# 06_-_INPUT.net
KiCad netlist of a schematic drawn in Altium Designer
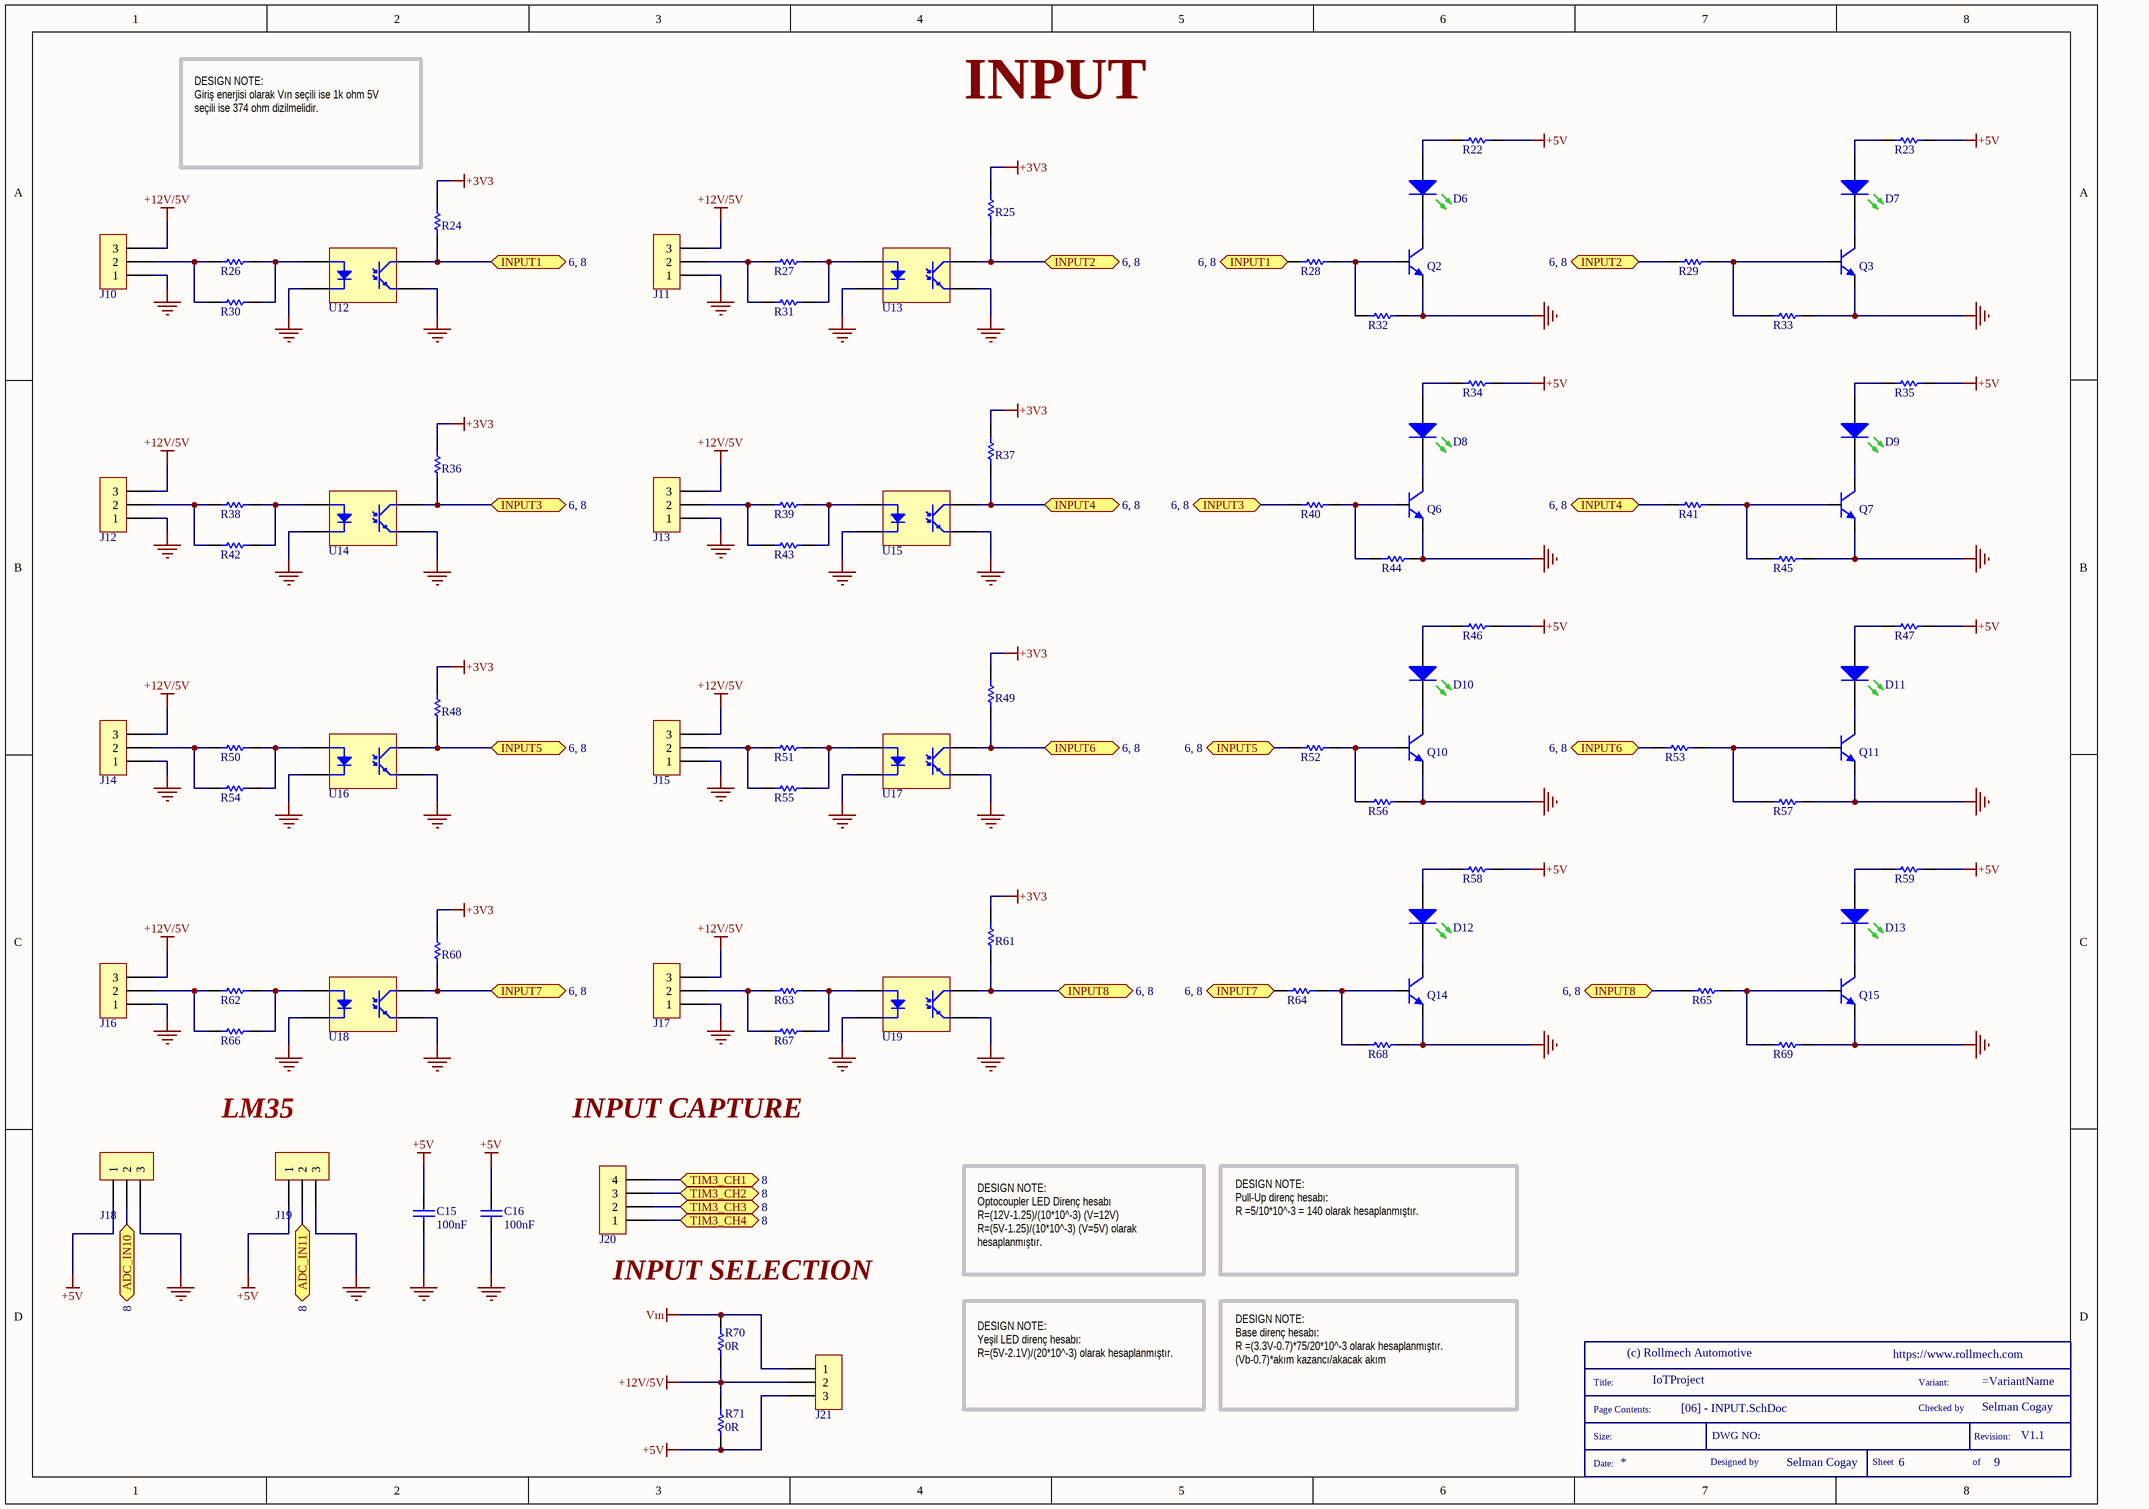
[diagram p0: [06] - INPUT.SchDoc]

(export (version "E")
  (design (tool "Eeschema 10.0.6"))
  (components
    (comp (ref "C15")
      (value "100nF")
      (footprint "C0603")
      (description "CAP CER 0.1UF 25V X7R 0603")
      (libsource (lib "SN65HVD2xx-CAN-Module-V1I1") (part "CGA3E2X7R1E104K080AA"))
    )
    (comp (ref "C16")
      (value "100nF")
      (footprint "C0603")
      (description "CAP CER 0.1UF 25V X7R 0603")
      (libsource (lib "SN65HVD2xx-CAN-Module-V1I1") (part "CGA3E2X7R1E104K080AA"))
    )
    (comp (ref "D6")
      (value "LED GREEN")
      (footprint "PLCC2")
      (description "LED TOPLED GREEN 562NM 2PLCC")
      (libsource (lib "Rollmech_Altium") (part "LP T67F-P1R2-35-1-20-R18-Z"))
    )
    (comp (ref "D7")
      (value "LED GREEN")
      (footprint "PLCC2")
      (description "LED TOPLED GREEN 562NM 2PLCC")
      (libsource (lib "Rollmech_Altium") (part "LP T67F-P1R2-35-1-20-R18-Z"))
    )
    (comp (ref "D8")
      (value "LED GREEN")
      (footprint "PLCC2")
      (description "LED TOPLED GREEN 562NM 2PLCC")
      (libsource (lib "Rollmech_Altium") (part "LP T67F-P1R2-35-1-20-R18-Z"))
    )
    (comp (ref "D9")
      (value "LED GREEN")
      (footprint "PLCC2")
      (description "LED TOPLED GREEN 562NM 2PLCC")
      (libsource (lib "Rollmech_Altium") (part "LP T67F-P1R2-35-1-20-R18-Z"))
    )
    (comp (ref "D10")
      (value "LED GREEN")
      (footprint "PLCC2")
      (description "LED TOPLED GREEN 562NM 2PLCC")
      (libsource (lib "Rollmech_Altium") (part "LP T67F-P1R2-35-1-20-R18-Z"))
    )
    (comp (ref "D11")
      (value "LED GREEN")
      (footprint "PLCC2")
      (description "LED TOPLED GREEN 562NM 2PLCC")
      (libsource (lib "Rollmech_Altium") (part "LP T67F-P1R2-35-1-20-R18-Z"))
    )
    (comp (ref "D12")
      (value "LED GREEN")
      (footprint "PLCC2")
      (description "LED TOPLED GREEN 562NM 2PLCC")
      (libsource (lib "Rollmech_Altium") (part "LP T67F-P1R2-35-1-20-R18-Z"))
    )
    (comp (ref "D13")
      (value "LED GREEN")
      (footprint "PLCC2")
      (description "LED TOPLED GREEN 562NM 2PLCC")
      (libsource (lib "Rollmech_Altium") (part "LP T67F-P1R2-35-1-20-R18-Z"))
    )
    (comp (ref "J10")
      (value "CONN 1X3 3MM")
      (footprint "CONN_MALE_1X3_3MM")
      (description "CONN MALE 1X3 3MM")
      (libsource (lib "Rollmech_Altium") (part "66200311122"))
    )
    (comp (ref "J11")
      (value "CONN 1X3 3MM")
      (footprint "CONN_MALE_1X3_3MM")
      (description "CONN MALE 1X3 3MM")
      (libsource (lib "Rollmech_Altium") (part "66200311122"))
    )
    (comp (ref "J12")
      (value "CONN 1X3 3MM")
      (footprint "CONN_MALE_1X3_3MM")
      (description "CONN MALE 1X3 3MM")
      (libsource (lib "Rollmech_Altium") (part "66200311122"))
    )
    (comp (ref "J13")
      (value "CONN 1X3 3MM")
      (footprint "CONN_MALE_1X3_3MM")
      (description "CONN MALE 1X3 3MM")
      (libsource (lib "Rollmech_Altium") (part "66200311122"))
    )
    (comp (ref "J14")
      (value "CONN 1X3 3MM")
      (footprint "CONN_MALE_1X3_3MM")
      (description "CONN MALE 1X3 3MM")
      (libsource (lib "Rollmech_Altium") (part "66200311122"))
    )
    (comp (ref "J15")
      (value "CONN 1X3 3MM")
      (footprint "CONN_MALE_1X3_3MM")
      (description "CONN MALE 1X3 3MM")
      (libsource (lib "Rollmech_Altium") (part "66200311122"))
    )
    (comp (ref "J16")
      (value "CONN 1X3 3MM")
      (footprint "CONN_MALE_1X3_3MM")
      (description "CONN MALE 1X3 3MM")
      (libsource (lib "Rollmech_Altium") (part "66200311122"))
    )
    (comp (ref "J17")
      (value "CONN 1X3 3MM")
      (footprint "CONN_MALE_1X3_3MM")
      (description "CONN MALE 1X3 3MM")
      (libsource (lib "Rollmech_Altium") (part "66200311122"))
    )
    (comp (ref "J18")
      (value "HDR_1X3_2.54")
      (footprint "HDR_MALE_1X3_2.54MM")
      (description "HDR MALE 1X3 2.54MM")
      (libsource (lib "Rollmech_Altium") (part "61300311121"))
    )
    (comp (ref "J19")
      (value "HDR_1X3_2.54")
      (footprint "HDR_MALE_1X3_2.54MM")
      (description "HDR MALE 1X3 2.54MM")
      (libsource (lib "Rollmech_Altium") (part "61300311121"))
    )
    (comp (ref "J20")
      (value "HDR FEMALE 1X4 2.54MM")
      (footprint "HDR_FEMALE_1X4_2.54MM")
      (libsource (lib "Rollmech_Altium") (part "PPTC041LFBN-RC"))
    )
    (comp (ref "J21")
      (value "HDR_1X3_2.54")
      (footprint "HDR_MALE_1X3_2.54MM")
      (description "HDR MALE 1X3 2.54MM")
      (libsource (lib "") (part "61300311121_1"))
    )
    (comp (ref "Q2")
      (value "NPN 0.6A")
      (footprint "SOT-23 (TO-236)")
      (description "TRANS NPN 40V 0.6A SMD SOT23-3")
      (libsource (lib "Rollmech_Altium") (part "MMBT2222A-7-F"))
    )
    (comp (ref "Q3")
      (value "NPN 0.6A")
      (footprint "SOT-23 (TO-236)")
      (description "TRANS NPN 40V 0.6A SMD SOT23-3")
      (libsource (lib "Rollmech_Altium") (part "MMBT2222A-7-F"))
    )
    (comp (ref "Q6")
      (value "NPN 0.6A")
      (footprint "SOT-23 (TO-236)")
      (description "TRANS NPN 40V 0.6A SMD SOT23-3")
      (libsource (lib "Rollmech_Altium") (part "MMBT2222A-7-F"))
    )
    (comp (ref "Q7")
      (value "NPN 0.6A")
      (footprint "SOT-23 (TO-236)")
      (description "TRANS NPN 40V 0.6A SMD SOT23-3")
      (libsource (lib "Rollmech_Altium") (part "MMBT2222A-7-F"))
    )
    (comp (ref "Q10")
      (value "NPN 0.6A")
      (footprint "SOT-23 (TO-236)")
      (description "TRANS NPN 40V 0.6A SMD SOT23-3")
      (libsource (lib "Rollmech_Altium") (part "MMBT2222A-7-F"))
    )
    (comp (ref "Q11")
      (value "NPN 0.6A")
      (footprint "SOT-23 (TO-236)")
      (description "TRANS NPN 40V 0.6A SMD SOT23-3")
      (libsource (lib "Rollmech_Altium") (part "MMBT2222A-7-F"))
    )
    (comp (ref "Q14")
      (value "NPN 0.6A")
      (footprint "SOT-23 (TO-236)")
      (description "TRANS NPN 40V 0.6A SMD SOT23-3")
      (libsource (lib "Rollmech_Altium") (part "MMBT2222A-7-F"))
    )
    (comp (ref "Q15")
      (value "NPN 0.6A")
      (footprint "SOT-23 (TO-236)")
      (description "TRANS NPN 40V 0.6A SMD SOT23-3")
      (libsource (lib "Rollmech_Altium") (part "MMBT2222A-7-F"))
    )
    (comp (ref "R22")
      (value "140 1/8W")
      (footprint "RES_0805")
      (description "RES SMD 140 OHM 1% 1/8W 0805")
      (libsource (lib "Rollmech_Altium") (part "ERJ-6ENF1400V"))
    )
    (comp (ref "R23")
      (value "140 1/8W")
      (footprint "RES_0805")
      (description "RES SMD 140 OHM 1% 1/8W 0805")
      (libsource (lib "Rollmech_Altium") (part "ERJ-6ENF1400V"))
    )
    (comp (ref "R24")
      (value "5.6k 1/8W")
      (footprint "RES_0805")
      (description "RES SMD 5.6K OHM 1% 1/8W 0805")
      (libsource (lib "Rollmech_Altium") (part "ERJ-6ENF5601V"))
    )
    (comp (ref "R25")
      (value "5.6k 1/8W")
      (footprint "RES_0805")
      (description "RES SMD 5.6K OHM 1% 1/8W 0805")
      (libsource (lib "Rollmech_Altium") (part "ERJ-6ENF5601V"))
    )
    (comp (ref "R26")
      (value "1K 1/8W")
      (footprint "RES_0805")
      (description "RES SMD 1K OHM")
      (libsource (lib "Rollmech_Altium") (part "ERJ-6ENF1001V"))
    )
    (comp (ref "R27")
      (value "1K 1/8W")
      (footprint "RES_0805")
      (description "RES SMD 1K OHM")
      (libsource (lib "Rollmech_Altium") (part "ERJ-6ENF1001V"))
    )
    (comp (ref "R28")
      (value "10K 1/8W")
      (footprint "RES_0805")
      (description "RES SMD 10K OHM 1% 1/8W 0805")
      (libsource (lib "Rollmech_Altium") (part "ERJ-6ENF1002V"))
    )
    (comp (ref "R29")
      (value "10K 1/8W")
      (footprint "RES_0805")
      (description "RES SMD 10K OHM 1% 1/8W 0805")
      (libsource (lib "Rollmech_Altium") (part "ERJ-6ENF1002V"))
    )
    (comp (ref "R30")
      (value "374 1/8W")
      (footprint "RES_0805")
      (description "RES SMD 374 OHM 1% 1/8W 0805")
      (libsource (lib "Rollmech_Altium") (part "ERJ-6ENF3740V"))
    )
    (comp (ref "R31")
      (value "374 1/8W")
      (footprint "RES_0805")
      (description "RES SMD 374 OHM 1% 1/8W 0805")
      (libsource (lib "Rollmech_Altium") (part "ERJ-6ENF3740V"))
    )
    (comp (ref "R32")
      (value "100K 1/4W")
      (footprint "RES_0603")
      (description "RES SMD 100K 5% 1/4W 0603")
      (libsource (lib "Rollmech_Altium") (part "ERJ-PA3J104V"))
    )
    (comp (ref "R33")
      (value "100K 1/4W")
      (footprint "RES_0603")
      (description "RES SMD 100K 5% 1/4W 0603")
      (libsource (lib "Rollmech_Altium") (part "ERJ-PA3J104V"))
    )
    (comp (ref "R34")
      (value "140 1/8W")
      (footprint "RES_0805")
      (description "RES SMD 140 OHM 1% 1/8W 0805")
      (libsource (lib "Rollmech_Altium") (part "ERJ-6ENF1400V"))
    )
    (comp (ref "R35")
      (value "140 1/8W")
      (footprint "RES_0805")
      (description "RES SMD 140 OHM 1% 1/8W 0805")
      (libsource (lib "Rollmech_Altium") (part "ERJ-6ENF1400V"))
    )
    (comp (ref "R36")
      (value "5.6k 1/8W")
      (footprint "RES_0805")
      (description "RES SMD 5.6K OHM 1% 1/8W 0805")
      (libsource (lib "Rollmech_Altium") (part "ERJ-6ENF5601V"))
    )
    (comp (ref "R37")
      (value "5.6k 1/8W")
      (footprint "RES_0805")
      (description "RES SMD 5.6K OHM 1% 1/8W 0805")
      (libsource (lib "Rollmech_Altium") (part "ERJ-6ENF5601V"))
    )
    (comp (ref "R38")
      (value "1K 1/8W")
      (footprint "RES_0805")
      (description "RES SMD 1K OHM")
      (libsource (lib "Rollmech_Altium") (part "ERJ-6ENF1001V"))
    )
    (comp (ref "R39")
      (value "1K 1/8W")
      (footprint "RES_0805")
      (description "RES SMD 1K OHM")
      (libsource (lib "Rollmech_Altium") (part "ERJ-6ENF1001V"))
    )
    (comp (ref "R40")
      (value "10K 1/8W")
      (footprint "RES_0805")
      (description "RES SMD 10K OHM 1% 1/8W 0805")
      (libsource (lib "Rollmech_Altium") (part "ERJ-6ENF1002V"))
    )
    (comp (ref "R41")
      (value "10K 1/8W")
      (footprint "RES_0805")
      (description "RES SMD 10K OHM 1% 1/8W 0805")
      (libsource (lib "Rollmech_Altium") (part "ERJ-6ENF1002V"))
    )
    (comp (ref "R42")
      (value "374 1/8W")
      (footprint "RES_0805")
      (description "RES SMD 374 OHM 1% 1/8W 0805")
      (libsource (lib "Rollmech_Altium") (part "ERJ-6ENF3740V"))
    )
    (comp (ref "R43")
      (value "374 1/8W")
      (footprint "RES_0805")
      (description "RES SMD 374 OHM 1% 1/8W 0805")
      (libsource (lib "Rollmech_Altium") (part "ERJ-6ENF3740V"))
    )
    (comp (ref "R44")
      (value "100K 1/4W")
      (footprint "RES_0603")
      (description "RES SMD 100K 5% 1/4W 0603")
      (libsource (lib "Rollmech_Altium") (part "ERJ-PA3J104V"))
    )
    (comp (ref "R45")
      (value "100K 1/4W")
      (footprint "RES_0603")
      (description "RES SMD 100K 5% 1/4W 0603")
      (libsource (lib "Rollmech_Altium") (part "ERJ-PA3J104V"))
    )
    (comp (ref "R46")
      (value "140 1/8W")
      (footprint "RES_0805")
      (description "RES SMD 140 OHM 1% 1/8W 0805")
      (libsource (lib "Rollmech_Altium") (part "ERJ-6ENF1400V"))
    )
    (comp (ref "R47")
      (value "140 1/8W")
      (footprint "RES_0805")
      (description "RES SMD 140 OHM 1% 1/8W 0805")
      (libsource (lib "Rollmech_Altium") (part "ERJ-6ENF1400V"))
    )
    (comp (ref "R48")
      (value "5.6k 1/8W")
      (footprint "RES_0805")
      (description "RES SMD 5.6K OHM 1% 1/8W 0805")
      (libsource (lib "Rollmech_Altium") (part "ERJ-6ENF5601V"))
    )
    (comp (ref "R49")
      (value "5.6k 1/8W")
      (footprint "RES_0805")
      (description "RES SMD 5.6K OHM 1% 1/8W 0805")
      (libsource (lib "Rollmech_Altium") (part "ERJ-6ENF5601V"))
    )
    (comp (ref "R50")
      (value "1K 1/8W")
      (footprint "RES_0805")
      (description "RES SMD 1K OHM")
      (libsource (lib "Rollmech_Altium") (part "ERJ-6ENF1001V"))
    )
    (comp (ref "R51")
      (value "1K 1/8W")
      (footprint "RES_0805")
      (description "RES SMD 1K OHM")
      (libsource (lib "Rollmech_Altium") (part "ERJ-6ENF1001V"))
    )
    (comp (ref "R52")
      (value "10K 1/8W")
      (footprint "RES_0805")
      (description "RES SMD 10K OHM 1% 1/8W 0805")
      (libsource (lib "Rollmech_Altium") (part "ERJ-6ENF1002V"))
    )
    (comp (ref "R53")
      (value "10K 1/8W")
      (footprint "RES_0805")
      (description "RES SMD 10K OHM 1% 1/8W 0805")
      (libsource (lib "Rollmech_Altium") (part "ERJ-6ENF1002V"))
    )
    (comp (ref "R54")
      (value "374 1/8W")
      (footprint "RES_0805")
      (description "RES SMD 374 OHM 1% 1/8W 0805")
      (libsource (lib "Rollmech_Altium") (part "ERJ-6ENF3740V"))
    )
    (comp (ref "R55")
      (value "374 1/8W")
      (footprint "RES_0805")
      (description "RES SMD 374 OHM 1% 1/8W 0805")
      (libsource (lib "Rollmech_Altium") (part "ERJ-6ENF3740V"))
    )
    (comp (ref "R56")
      (value "100K 1/4W")
      (footprint "RES_0603")
      (description "RES SMD 100K 5% 1/4W 0603")
      (libsource (lib "Rollmech_Altium") (part "ERJ-PA3J104V"))
    )
    (comp (ref "R57")
      (value "100K 1/4W")
      (footprint "RES_0603")
      (description "RES SMD 100K 5% 1/4W 0603")
      (libsource (lib "Rollmech_Altium") (part "ERJ-PA3J104V"))
    )
    (comp (ref "R58")
      (value "140 1/8W")
      (footprint "RES_0805")
      (description "RES SMD 140 OHM 1% 1/8W 0805")
      (libsource (lib "Rollmech_Altium") (part "ERJ-6ENF1400V"))
    )
    (comp (ref "R59")
      (value "140 1/8W")
      (footprint "RES_0805")
      (description "RES SMD 140 OHM 1% 1/8W 0805")
      (libsource (lib "Rollmech_Altium") (part "ERJ-6ENF1400V"))
    )
    (comp (ref "R60")
      (value "5.6k 1/8W")
      (footprint "RES_0805")
      (description "RES SMD 5.6K OHM 1% 1/8W 0805")
      (libsource (lib "Rollmech_Altium") (part "ERJ-6ENF5601V"))
    )
    (comp (ref "R61")
      (value "5.6k 1/8W")
      (footprint "RES_0805")
      (description "RES SMD 5.6K OHM 1% 1/8W 0805")
      (libsource (lib "Rollmech_Altium") (part "ERJ-6ENF5601V"))
    )
    (comp (ref "R62")
      (value "1K 1/8W")
      (footprint "RES_0805")
      (description "RES SMD 1K OHM")
      (libsource (lib "Rollmech_Altium") (part "ERJ-6ENF1001V"))
    )
    (comp (ref "R63")
      (value "1K 1/8W")
      (footprint "RES_0805")
      (description "RES SMD 1K OHM")
      (libsource (lib "Rollmech_Altium") (part "ERJ-6ENF1001V"))
    )
    (comp (ref "R64")
      (value "10K 1/8W")
      (footprint "RES_0805")
      (description "RES SMD 10K OHM 1% 1/8W 0805")
      (libsource (lib "Rollmech_Altium") (part "ERJ-6ENF1002V"))
    )
    (comp (ref "R65")
      (value "10K 1/8W")
      (footprint "RES_0805")
      (description "RES SMD 10K OHM 1% 1/8W 0805")
      (libsource (lib "Rollmech_Altium") (part "ERJ-6ENF1002V"))
    )
    (comp (ref "R66")
      (value "374 1/8W")
      (footprint "RES_0805")
      (description "RES SMD 374 OHM 1% 1/8W 0805")
      (libsource (lib "Rollmech_Altium") (part "ERJ-6ENF3740V"))
    )
    (comp (ref "R67")
      (value "374 1/8W")
      (footprint "RES_0805")
      (description "RES SMD 374 OHM 1% 1/8W 0805")
      (libsource (lib "Rollmech_Altium") (part "ERJ-6ENF3740V"))
    )
    (comp (ref "R68")
      (value "100K 1/4W")
      (footprint "RES_0603")
      (description "RES SMD 100K 5% 1/4W 0603")
      (libsource (lib "Rollmech_Altium") (part "ERJ-PA3J104V"))
    )
    (comp (ref "R69")
      (value "100K 1/4W")
      (footprint "RES_0603")
      (description "RES SMD 100K 5% 1/4W 0603")
      (libsource (lib "Rollmech_Altium") (part "ERJ-PA3J104V"))
    )
    (comp (ref "R70")
      (value "0R")
      (footprint "R0805")
      (description "RES SMD 0 OHM JUMPER 1/8W 0805")
      (libsource (lib "SN65HVD2xx-CAN-Module-V1I1") (part "CRCW08050000Z0EA"))
    )
    (comp (ref "R71")
      (value "0R")
      (footprint "R0805")
      (description "RES SMD 0 OHM JUMPER 1/8W 0805")
      (libsource (lib "SN65HVD2xx-CAN-Module-V1I1") (part "CRCW08050000Z0EA"))
    )
    (comp (ref "U12")
      (value "NPN 3.75KV")
      (footprint "SOIC-6")
      (description "OPTOISO 3.75KV TRANS")
      (libsource (lib "Rollmech_Altium") (part "TLP2301(TPL,E"))
    )
    (comp (ref "U13")
      (value "NPN 3.75KV")
      (footprint "SOIC-6")
      (description "OPTOISO 3.75KV TRANS")
      (libsource (lib "Rollmech_Altium") (part "TLP2301(TPL,E"))
    )
    (comp (ref "U14")
      (value "NPN 3.75KV")
      (footprint "SOIC-6")
      (description "OPTOISO 3.75KV TRANS")
      (libsource (lib "Rollmech_Altium") (part "TLP2301(TPL,E"))
    )
    (comp (ref "U15")
      (value "NPN 3.75KV")
      (footprint "SOIC-6")
      (description "OPTOISO 3.75KV TRANS")
      (libsource (lib "Rollmech_Altium") (part "TLP2301(TPL,E"))
    )
    (comp (ref "U16")
      (value "NPN 3.75KV")
      (footprint "SOIC-6")
      (description "OPTOISO 3.75KV TRANS")
      (libsource (lib "Rollmech_Altium") (part "TLP2301(TPL,E"))
    )
    (comp (ref "U17")
      (value "NPN 3.75KV")
      (footprint "SOIC-6")
      (description "OPTOISO 3.75KV TRANS")
      (libsource (lib "Rollmech_Altium") (part "TLP2301(TPL,E"))
    )
    (comp (ref "U18")
      (value "NPN 3.75KV")
      (footprint "SOIC-6")
      (description "OPTOISO 3.75KV TRANS")
      (libsource (lib "Rollmech_Altium") (part "TLP2301(TPL,E"))
    )
    (comp (ref "U19")
      (value "NPN 3.75KV")
      (footprint "SOIC-6")
      (description "OPTOISO 3.75KV TRANS")
      (libsource (lib "Rollmech_Altium") (part "TLP2301(TPL,E"))
    )
  )
  (nets
    (net (code "1") (name "+3V3") (class "Default")
      (node (ref "R24") (pin "2") (pinfunction "2_2") (pintype "passive"))
      (node (ref "R25") (pin "2") (pinfunction "2_2") (pintype "passive"))
      (node (ref "R36") (pin "2") (pinfunction "2_2") (pintype "passive"))
      (node (ref "R37") (pin "2") (pinfunction "2_2") (pintype "passive"))
      (node (ref "R48") (pin "2") (pinfunction "2_2") (pintype "passive"))
      (node (ref "R49") (pin "2") (pinfunction "2_2") (pintype "passive"))
      (node (ref "R60") (pin "2") (pinfunction "2_2") (pintype "passive"))
      (node (ref "R61") (pin "2") (pinfunction "2_2") (pintype "passive"))
    )
    (net (code "2") (name "+5V") (class "Default")
      (node (ref "C15") (pin "2") (pinfunction "2_2") (pintype "passive"))
      (node (ref "C16") (pin "2") (pinfunction "2_2") (pintype "passive"))
      (node (ref "J18") (pin "1") (pinfunction "1_1") (pintype "passive"))
      (node (ref "J19") (pin "1") (pinfunction "1_1") (pintype "passive"))
      (node (ref "J21") (pin "3") (pinfunction "3_3") (pintype "passive"))
      (node (ref "R22") (pin "2") (pinfunction "2_2") (pintype "passive"))
      (node (ref "R23") (pin "2") (pinfunction "2_2") (pintype "passive"))
      (node (ref "R34") (pin "2") (pinfunction "2_2") (pintype "passive"))
      (node (ref "R35") (pin "2") (pinfunction "2_2") (pintype "passive"))
      (node (ref "R46") (pin "2") (pinfunction "2_2") (pintype "passive"))
      (node (ref "R47") (pin "2") (pinfunction "2_2") (pintype "passive"))
      (node (ref "R58") (pin "2") (pinfunction "2_2") (pintype "passive"))
      (node (ref "R59") (pin "2") (pinfunction "2_2") (pintype "passive"))
      (node (ref "R71") (pin "1") (pinfunction "1_1") (pintype "passive"))
    )
    (net (code "3") (name "+12V{slash}5V") (class "Default")
      (node (ref "J10") (pin "3") (pinfunction "3_3") (pintype "passive"))
      (node (ref "J11") (pin "3") (pinfunction "3_3") (pintype "passive"))
      (node (ref "J12") (pin "3") (pinfunction "3_3") (pintype "passive"))
      (node (ref "J13") (pin "3") (pinfunction "3_3") (pintype "passive"))
      (node (ref "J14") (pin "3") (pinfunction "3_3") (pintype "passive"))
      (node (ref "J15") (pin "3") (pinfunction "3_3") (pintype "passive"))
      (node (ref "J16") (pin "3") (pinfunction "3_3") (pintype "passive"))
      (node (ref "J17") (pin "3") (pinfunction "3_3") (pintype "passive"))
      (node (ref "J21") (pin "2") (pinfunction "2_2") (pintype "passive"))
      (node (ref "R70") (pin "1") (pinfunction "1_1") (pintype "passive"))
      (node (ref "R71") (pin "2") (pinfunction "2_2") (pintype "passive"))
    )
    (net (code "4") (name "/ADC_IN10") (class "Default")
      (node (ref "J18") (pin "2") (pinfunction "2_2") (pintype "passive"))
    )
    (net (code "5") (name "/ADC_IN11") (class "Default")
      (node (ref "J19") (pin "2") (pinfunction "2_2") (pintype "passive"))
    )
    (net (code "6") (name "/INPUT1") (class "Default")
      (node (ref "R24") (pin "1") (pinfunction "1_1") (pintype "passive"))
      (node (ref "R28") (pin "1") (pinfunction "1_1") (pintype "passive"))
      (node (ref "U12") (pin "6") (pinfunction "Coll_6") (pintype "passive"))
    )
    (net (code "7") (name "/INPUT2") (class "Default")
      (node (ref "R25") (pin "1") (pinfunction "1_1") (pintype "passive"))
      (node (ref "R29") (pin "1") (pinfunction "1_1") (pintype "passive"))
      (node (ref "U13") (pin "6") (pinfunction "Coll_6") (pintype "passive"))
    )
    (net (code "8") (name "/INPUT3") (class "Default")
      (node (ref "R36") (pin "1") (pinfunction "1_1") (pintype "passive"))
      (node (ref "R40") (pin "1") (pinfunction "1_1") (pintype "passive"))
      (node (ref "U14") (pin "6") (pinfunction "Coll_6") (pintype "passive"))
    )
    (net (code "9") (name "/INPUT4") (class "Default")
      (node (ref "R37") (pin "1") (pinfunction "1_1") (pintype "passive"))
      (node (ref "R41") (pin "1") (pinfunction "1_1") (pintype "passive"))
      (node (ref "U15") (pin "6") (pinfunction "Coll_6") (pintype "passive"))
    )
    (net (code "10") (name "/INPUT5") (class "Default")
      (node (ref "R48") (pin "1") (pinfunction "1_1") (pintype "passive"))
      (node (ref "R52") (pin "1") (pinfunction "1_1") (pintype "passive"))
      (node (ref "U16") (pin "6") (pinfunction "Coll_6") (pintype "passive"))
    )
    (net (code "11") (name "/INPUT6") (class "Default")
      (node (ref "R49") (pin "1") (pinfunction "1_1") (pintype "passive"))
      (node (ref "R53") (pin "1") (pinfunction "1_1") (pintype "passive"))
      (node (ref "U17") (pin "6") (pinfunction "Coll_6") (pintype "passive"))
    )
    (net (code "12") (name "/INPUT7") (class "Default")
      (node (ref "R60") (pin "1") (pinfunction "1_1") (pintype "passive"))
      (node (ref "R64") (pin "1") (pinfunction "1_1") (pintype "passive"))
      (node (ref "U18") (pin "6") (pinfunction "Coll_6") (pintype "passive"))
    )
    (net (code "13") (name "/INPUT8") (class "Default")
      (node (ref "R61") (pin "1") (pinfunction "1_1") (pintype "passive"))
      (node (ref "R65") (pin "1") (pinfunction "1_1") (pintype "passive"))
      (node (ref "U19") (pin "6") (pinfunction "Coll_6") (pintype "passive"))
    )
    (net (code "14") (name "/TIM3_CH1") (class "Default")
      (node (ref "J20") (pin "4") (pinfunction "4_4") (pintype "passive"))
    )
    (net (code "15") (name "/TIM3_CH2") (class "Default")
      (node (ref "J20") (pin "3") (pinfunction "3_3") (pintype "passive"))
    )
    (net (code "16") (name "/TIM3_CH3") (class "Default")
      (node (ref "J20") (pin "2") (pinfunction "2_2") (pintype "passive"))
    )
    (net (code "17") (name "/TIM3_CH4") (class "Default")
      (node (ref "J20") (pin "1") (pinfunction "1_1") (pintype "passive"))
    )
    (net (code "18") (name "GND") (class "Default")
      (node (ref "C15") (pin "1") (pinfunction "1_1") (pintype "passive"))
      (node (ref "C16") (pin "1") (pinfunction "1_1") (pintype "passive"))
      (node (ref "J10") (pin "1") (pinfunction "1_1") (pintype "passive"))
      (node (ref "J11") (pin "1") (pinfunction "1_1") (pintype "passive"))
      (node (ref "J12") (pin "1") (pinfunction "1_1") (pintype "passive"))
      (node (ref "J13") (pin "1") (pinfunction "1_1") (pintype "passive"))
      (node (ref "J14") (pin "1") (pinfunction "1_1") (pintype "passive"))
      (node (ref "J15") (pin "1") (pinfunction "1_1") (pintype "passive"))
      (node (ref "J16") (pin "1") (pinfunction "1_1") (pintype "passive"))
      (node (ref "J17") (pin "1") (pinfunction "1_1") (pintype "passive"))
      (node (ref "J18") (pin "3") (pinfunction "3_3") (pintype "passive"))
      (node (ref "J19") (pin "3") (pinfunction "3_3") (pintype "passive"))
      (node (ref "Q10") (pin "3") (pinfunction "E_3") (pintype "passive"))
      (node (ref "Q11") (pin "3") (pinfunction "E_3") (pintype "passive"))
      (node (ref "Q14") (pin "3") (pinfunction "E_3") (pintype "passive"))
      (node (ref "Q15") (pin "3") (pinfunction "E_3") (pintype "passive"))
      (node (ref "Q2") (pin "3") (pinfunction "E_3") (pintype "passive"))
      (node (ref "Q3") (pin "3") (pinfunction "E_3") (pintype "passive"))
      (node (ref "Q6") (pin "3") (pinfunction "E_3") (pintype "passive"))
      (node (ref "Q7") (pin "3") (pinfunction "E_3") (pintype "passive"))
      (node (ref "R32") (pin "2") (pinfunction "2_2") (pintype "passive"))
      (node (ref "R33") (pin "2") (pinfunction "2_2") (pintype "passive"))
      (node (ref "R44") (pin "2") (pinfunction "2_2") (pintype "passive"))
      (node (ref "R45") (pin "2") (pinfunction "2_2") (pintype "passive"))
      (node (ref "R56") (pin "2") (pinfunction "2_2") (pintype "passive"))
      (node (ref "R57") (pin "2") (pinfunction "2_2") (pintype "passive"))
      (node (ref "R68") (pin "2") (pinfunction "2_2") (pintype "passive"))
      (node (ref "R69") (pin "2") (pinfunction "2_2") (pintype "passive"))
      (node (ref "U12") (pin "3") (pinfunction "K_3") (pintype "passive"))
      (node (ref "U12") (pin "4") (pinfunction "Emit_4") (pintype "passive"))
      (node (ref "U13") (pin "3") (pinfunction "K_3") (pintype "passive"))
      (node (ref "U13") (pin "4") (pinfunction "Emit_4") (pintype "passive"))
      (node (ref "U14") (pin "3") (pinfunction "K_3") (pintype "passive"))
      (node (ref "U14") (pin "4") (pinfunction "Emit_4") (pintype "passive"))
      (node (ref "U15") (pin "3") (pinfunction "K_3") (pintype "passive"))
      (node (ref "U15") (pin "4") (pinfunction "Emit_4") (pintype "passive"))
      (node (ref "U16") (pin "3") (pinfunction "K_3") (pintype "passive"))
      (node (ref "U16") (pin "4") (pinfunction "Emit_4") (pintype "passive"))
      (node (ref "U17") (pin "3") (pinfunction "K_3") (pintype "passive"))
      (node (ref "U17") (pin "4") (pinfunction "Emit_4") (pintype "passive"))
      (node (ref "U18") (pin "3") (pinfunction "K_3") (pintype "passive"))
      (node (ref "U18") (pin "4") (pinfunction "Emit_4") (pintype "passive"))
      (node (ref "U19") (pin "3") (pinfunction "K_3") (pintype "passive"))
      (node (ref "U19") (pin "4") (pinfunction "Emit_4") (pintype "passive"))
    )
    (net (code "19") (name "Net-(D6-A)") (class "Default")
      (node (ref "D6") (pin "1") (pinfunction "A_1") (pintype "passive"))
      (node (ref "R22") (pin "1") (pinfunction "1_1") (pintype "passive"))
    )
    (net (code "20") (name "Net-(D6-K)") (class "Default")
      (node (ref "D6") (pin "2") (pinfunction "K_2") (pintype "passive"))
      (node (ref "Q2") (pin "1") (pinfunction "C_1") (pintype "passive"))
    )
    (net (code "21") (name "Net-(D7-A)") (class "Default")
      (node (ref "D7") (pin "1") (pinfunction "A_1") (pintype "passive"))
      (node (ref "R23") (pin "1") (pinfunction "1_1") (pintype "passive"))
    )
    (net (code "22") (name "Net-(D7-K)") (class "Default")
      (node (ref "D7") (pin "2") (pinfunction "K_2") (pintype "passive"))
      (node (ref "Q3") (pin "1") (pinfunction "C_1") (pintype "passive"))
    )
    (net (code "23") (name "Net-(D8-A)") (class "Default")
      (node (ref "D8") (pin "1") (pinfunction "A_1") (pintype "passive"))
      (node (ref "R34") (pin "1") (pinfunction "1_1") (pintype "passive"))
    )
    (net (code "24") (name "Net-(D8-K)") (class "Default")
      (node (ref "D8") (pin "2") (pinfunction "K_2") (pintype "passive"))
      (node (ref "Q6") (pin "1") (pinfunction "C_1") (pintype "passive"))
    )
    (net (code "25") (name "Net-(D9-A)") (class "Default")
      (node (ref "D9") (pin "1") (pinfunction "A_1") (pintype "passive"))
      (node (ref "R35") (pin "1") (pinfunction "1_1") (pintype "passive"))
    )
    (net (code "26") (name "Net-(D9-K)") (class "Default")
      (node (ref "D9") (pin "2") (pinfunction "K_2") (pintype "passive"))
      (node (ref "Q7") (pin "1") (pinfunction "C_1") (pintype "passive"))
    )
    (net (code "27") (name "Net-(D10-A)") (class "Default")
      (node (ref "D10") (pin "1") (pinfunction "A_1") (pintype "passive"))
      (node (ref "R46") (pin "1") (pinfunction "1_1") (pintype "passive"))
    )
    (net (code "28") (name "Net-(D10-K)") (class "Default")
      (node (ref "D10") (pin "2") (pinfunction "K_2") (pintype "passive"))
      (node (ref "Q10") (pin "1") (pinfunction "C_1") (pintype "passive"))
    )
    (net (code "29") (name "Net-(D11-A)") (class "Default")
      (node (ref "D11") (pin "1") (pinfunction "A_1") (pintype "passive"))
      (node (ref "R47") (pin "1") (pinfunction "1_1") (pintype "passive"))
    )
    (net (code "30") (name "Net-(D11-K)") (class "Default")
      (node (ref "D11") (pin "2") (pinfunction "K_2") (pintype "passive"))
      (node (ref "Q11") (pin "1") (pinfunction "C_1") (pintype "passive"))
    )
    (net (code "31") (name "Net-(D12-A)") (class "Default")
      (node (ref "D12") (pin "1") (pinfunction "A_1") (pintype "passive"))
      (node (ref "R58") (pin "1") (pinfunction "1_1") (pintype "passive"))
    )
    (net (code "32") (name "Net-(D12-K)") (class "Default")
      (node (ref "D12") (pin "2") (pinfunction "K_2") (pintype "passive"))
      (node (ref "Q14") (pin "1") (pinfunction "C_1") (pintype "passive"))
    )
    (net (code "33") (name "Net-(D13-A)") (class "Default")
      (node (ref "D13") (pin "1") (pinfunction "A_1") (pintype "passive"))
      (node (ref "R59") (pin "1") (pinfunction "1_1") (pintype "passive"))
    )
    (net (code "34") (name "Net-(D13-K)") (class "Default")
      (node (ref "D13") (pin "2") (pinfunction "K_2") (pintype "passive"))
      (node (ref "Q15") (pin "1") (pinfunction "C_1") (pintype "passive"))
    )
    (net (code "35") (name "Net-(J10-Pad2)") (class "Default")
      (node (ref "J10") (pin "2") (pinfunction "2_2") (pintype "passive"))
      (node (ref "R26") (pin "1") (pinfunction "1_1") (pintype "passive"))
      (node (ref "R30") (pin "1") (pinfunction "1_1") (pintype "passive"))
    )
    (net (code "36") (name "Net-(J11-Pad2)") (class "Default")
      (node (ref "J11") (pin "2") (pinfunction "2_2") (pintype "passive"))
      (node (ref "R27") (pin "1") (pinfunction "1_1") (pintype "passive"))
      (node (ref "R31") (pin "1") (pinfunction "1_1") (pintype "passive"))
    )
    (net (code "37") (name "Net-(J12-Pad2)") (class "Default")
      (node (ref "J12") (pin "2") (pinfunction "2_2") (pintype "passive"))
      (node (ref "R38") (pin "1") (pinfunction "1_1") (pintype "passive"))
      (node (ref "R42") (pin "1") (pinfunction "1_1") (pintype "passive"))
    )
    (net (code "38") (name "Net-(J13-Pad2)") (class "Default")
      (node (ref "J13") (pin "2") (pinfunction "2_2") (pintype "passive"))
      (node (ref "R39") (pin "1") (pinfunction "1_1") (pintype "passive"))
      (node (ref "R43") (pin "1") (pinfunction "1_1") (pintype "passive"))
    )
    (net (code "39") (name "Net-(J14-Pad2)") (class "Default")
      (node (ref "J14") (pin "2") (pinfunction "2_2") (pintype "passive"))
      (node (ref "R50") (pin "1") (pinfunction "1_1") (pintype "passive"))
      (node (ref "R54") (pin "1") (pinfunction "1_1") (pintype "passive"))
    )
    (net (code "40") (name "Net-(J15-Pad2)") (class "Default")
      (node (ref "J15") (pin "2") (pinfunction "2_2") (pintype "passive"))
      (node (ref "R51") (pin "1") (pinfunction "1_1") (pintype "passive"))
      (node (ref "R55") (pin "1") (pinfunction "1_1") (pintype "passive"))
    )
    (net (code "41") (name "Net-(J16-Pad2)") (class "Default")
      (node (ref "J16") (pin "2") (pinfunction "2_2") (pintype "passive"))
      (node (ref "R62") (pin "1") (pinfunction "1_1") (pintype "passive"))
      (node (ref "R66") (pin "1") (pinfunction "1_1") (pintype "passive"))
    )
    (net (code "42") (name "Net-(J17-Pad2)") (class "Default")
      (node (ref "J17") (pin "2") (pinfunction "2_2") (pintype "passive"))
      (node (ref "R63") (pin "1") (pinfunction "1_1") (pintype "passive"))
      (node (ref "R67") (pin "1") (pinfunction "1_1") (pintype "passive"))
    )
    (net (code "43") (name "Net-(Q2-B)") (class "Default")
      (node (ref "Q2") (pin "2") (pinfunction "B_2") (pintype "passive"))
      (node (ref "R28") (pin "2") (pinfunction "2_2") (pintype "passive"))
      (node (ref "R32") (pin "1") (pinfunction "1_1") (pintype "passive"))
    )
    (net (code "44") (name "Net-(Q3-B)") (class "Default")
      (node (ref "Q3") (pin "2") (pinfunction "B_2") (pintype "passive"))
      (node (ref "R29") (pin "2") (pinfunction "2_2") (pintype "passive"))
      (node (ref "R33") (pin "1") (pinfunction "1_1") (pintype "passive"))
    )
    (net (code "45") (name "Net-(Q6-B)") (class "Default")
      (node (ref "Q6") (pin "2") (pinfunction "B_2") (pintype "passive"))
      (node (ref "R40") (pin "2") (pinfunction "2_2") (pintype "passive"))
      (node (ref "R44") (pin "1") (pinfunction "1_1") (pintype "passive"))
    )
    (net (code "46") (name "Net-(Q7-B)") (class "Default")
      (node (ref "Q7") (pin "2") (pinfunction "B_2") (pintype "passive"))
      (node (ref "R41") (pin "2") (pinfunction "2_2") (pintype "passive"))
      (node (ref "R45") (pin "1") (pinfunction "1_1") (pintype "passive"))
    )
    (net (code "47") (name "Net-(Q10-B)") (class "Default")
      (node (ref "Q10") (pin "2") (pinfunction "B_2") (pintype "passive"))
      (node (ref "R52") (pin "2") (pinfunction "2_2") (pintype "passive"))
      (node (ref "R56") (pin "1") (pinfunction "1_1") (pintype "passive"))
    )
    (net (code "48") (name "Net-(Q11-B)") (class "Default")
      (node (ref "Q11") (pin "2") (pinfunction "B_2") (pintype "passive"))
      (node (ref "R53") (pin "2") (pinfunction "2_2") (pintype "passive"))
      (node (ref "R57") (pin "1") (pinfunction "1_1") (pintype "passive"))
    )
    (net (code "49") (name "Net-(Q14-B)") (class "Default")
      (node (ref "Q14") (pin "2") (pinfunction "B_2") (pintype "passive"))
      (node (ref "R64") (pin "2") (pinfunction "2_2") (pintype "passive"))
      (node (ref "R68") (pin "1") (pinfunction "1_1") (pintype "passive"))
    )
    (net (code "50") (name "Net-(Q15-B)") (class "Default")
      (node (ref "Q15") (pin "2") (pinfunction "B_2") (pintype "passive"))
      (node (ref "R65") (pin "2") (pinfunction "2_2") (pintype "passive"))
      (node (ref "R69") (pin "1") (pinfunction "1_1") (pintype "passive"))
    )
    (net (code "51") (name "Net-(U12-A)") (class "Default")
      (node (ref "R26") (pin "2") (pinfunction "2_2") (pintype "passive"))
      (node (ref "R30") (pin "2") (pinfunction "2_2") (pintype "passive"))
      (node (ref "U12") (pin "1") (pinfunction "A_1") (pintype "passive"))
    )
    (net (code "52") (name "Net-(U13-A)") (class "Default")
      (node (ref "R27") (pin "2") (pinfunction "2_2") (pintype "passive"))
      (node (ref "R31") (pin "2") (pinfunction "2_2") (pintype "passive"))
      (node (ref "U13") (pin "1") (pinfunction "A_1") (pintype "passive"))
    )
    (net (code "53") (name "Net-(U14-A)") (class "Default")
      (node (ref "R38") (pin "2") (pinfunction "2_2") (pintype "passive"))
      (node (ref "R42") (pin "2") (pinfunction "2_2") (pintype "passive"))
      (node (ref "U14") (pin "1") (pinfunction "A_1") (pintype "passive"))
    )
    (net (code "54") (name "Net-(U15-A)") (class "Default")
      (node (ref "R39") (pin "2") (pinfunction "2_2") (pintype "passive"))
      (node (ref "R43") (pin "2") (pinfunction "2_2") (pintype "passive"))
      (node (ref "U15") (pin "1") (pinfunction "A_1") (pintype "passive"))
    )
    (net (code "55") (name "Net-(U16-A)") (class "Default")
      (node (ref "R50") (pin "2") (pinfunction "2_2") (pintype "passive"))
      (node (ref "R54") (pin "2") (pinfunction "2_2") (pintype "passive"))
      (node (ref "U16") (pin "1") (pinfunction "A_1") (pintype "passive"))
    )
    (net (code "56") (name "Net-(U17-A)") (class "Default")
      (node (ref "R51") (pin "2") (pinfunction "2_2") (pintype "passive"))
      (node (ref "R55") (pin "2") (pinfunction "2_2") (pintype "passive"))
      (node (ref "U17") (pin "1") (pinfunction "A_1") (pintype "passive"))
    )
    (net (code "57") (name "Net-(U18-A)") (class "Default")
      (node (ref "R62") (pin "2") (pinfunction "2_2") (pintype "passive"))
      (node (ref "R66") (pin "2") (pinfunction "2_2") (pintype "passive"))
      (node (ref "U18") (pin "1") (pinfunction "A_1") (pintype "passive"))
    )
    (net (code "58") (name "Net-(U19-A)") (class "Default")
      (node (ref "R63") (pin "2") (pinfunction "2_2") (pintype "passive"))
      (node (ref "R67") (pin "2") (pinfunction "2_2") (pintype "passive"))
      (node (ref "U19") (pin "1") (pinfunction "A_1") (pintype "passive"))
    )
    (net (code "59") (name "Vın") (class "Default")
      (node (ref "J21") (pin "1") (pinfunction "1_1") (pintype "passive"))
      (node (ref "R70") (pin "2") (pinfunction "2_2") (pintype "passive"))
    )
  )
)
